# C_lula_2.net
KiCad netlist of a schematic drawn in Altium Designer
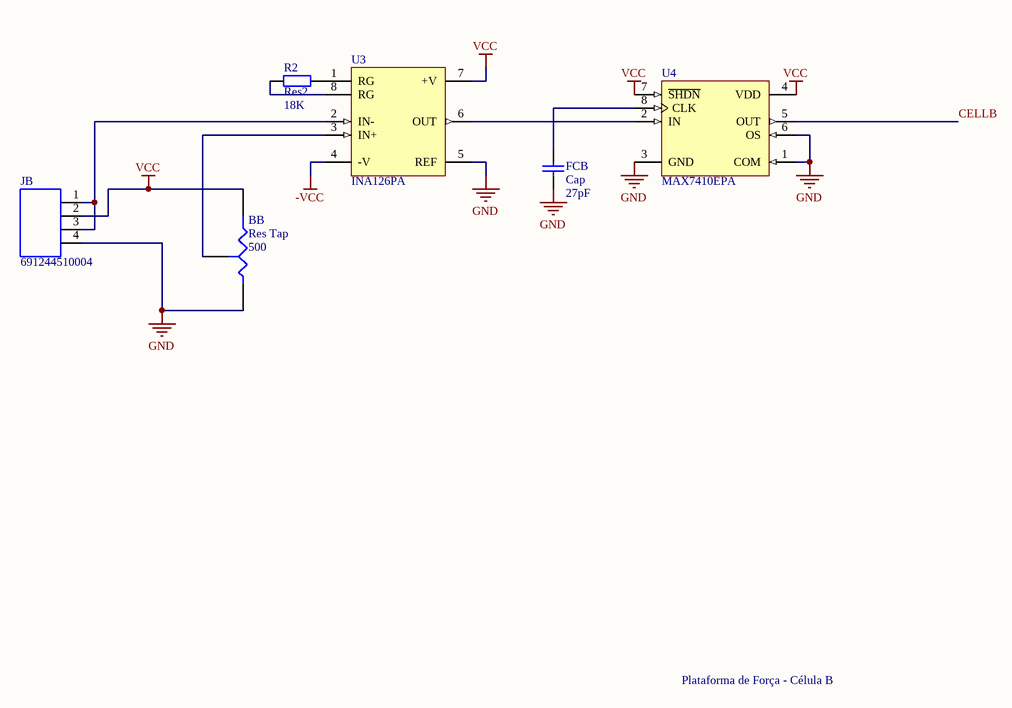
[diagram p0: Célula 2.SchDoc]

(export (version "E")
  (design (tool "Eeschema 10.0.6"))
  (components
    (comp (ref "BB")
      (value "Res Tap")
      (footprint "PcbLib1:TSR3006")
      (description "Tapped Resistor")
      (fields (field (name "ALTIUM_VALUE") "500") (field (name "PUBLISHER") "Altium Limited"))
      (libsource (lib "Miscellaneous Devices") (part "Res Tap"))
    )
    (comp (ref "FCB")
      (value "Cap")
      (footprint "RAD-0.3")
      (description "Capacitor")
      (fields (field (name "ALTIUM_VALUE") "27pF") (field (name "PUBLISHER") "Altium Limited"))
      (libsource (lib "Miscellaneous Devices") (part "Cap"))
    )
    (comp (ref "JB")
      (value "691244510004")
      (footprint "691244510004")
      (description "WR-TBL Horizontal Cable Entry With Rising Cage Clamp,Serie 2445 - 5.08 mm")
      (fields (field (name "MANUFACTURER") "Wurth Elektronik") (field (name "CREATED BY") "Baojun Chen"))
      (libsource (lib "WE_WR-TBL_Rising Cage System_5.08 mm_rev15b") (part "691244510004"))
    )
    (comp (ref "R2")
      (value "Res2")
      (footprint "AXIAL-0.4")
      (description "Resistor")
      (fields (field (name "ALTIUM_VALUE") "18K") (field (name "PUBLISHER") "Altium Limited"))
      (libsource (lib "Miscellaneous Devices") (part "Res2"))
    )
    (comp (ref "U3")
      (value "INA126PA")
      (footprint "006E")
      (description "Precision, Low-Power Instrumentation Amplifiers")
      (fields (field (name "PUBLISHER") "Altium Limited"))
      (libsource (lib "Placa") (part "INA126PA"))
    )
    (comp (ref "U4")
      (value "MAX7410EPA")
      (footprint "PA8")
      (description "5th-Order, Lowpass, Switched-Capacitor Filter")
      (fields (field (name "PUBLISHER") "Altium Limited"))
      (libsource (lib "Maxim Filter Switched Capacitor") (part "MAX7410EPA"))
    )
  )
  (nets
    (net (code "1") (name "-VCC") (class "Default")
      (node (ref "U3") (pin "4") (pinfunction "-V_4") (pintype "power_in"))
    )
    (net (code "2") (name "/CELLB") (class "Default")
      (node (ref "U4") (pin "5") (pinfunction "OUT_5") (pintype "output"))
    )
    (net (code "3") (name "GND") (class "Default")
      (node (ref "BB") (pin "1") (pinfunction "A_1") (pintype "passive"))
      (node (ref "FCB") (pin "1") (pinfunction "1_1") (pintype "passive"))
      (node (ref "JB") (pin "4") (pinfunction "4_4") (pintype "passive"))
      (node (ref "U3") (pin "5") (pinfunction "REF_5") (pintype "passive"))
      (node (ref "U4") (pin "1") (pinfunction "COM_1") (pintype "input"))
      (node (ref "U4") (pin "3") (pinfunction "GND_3") (pintype "power_in"))
      (node (ref "U4") (pin "6") (pinfunction "OS_6") (pintype "input"))
    )
    (net (code "4") (name "Net-(BB-TAP)") (class "Default")
      (node (ref "BB") (pin "3") (pinfunction "TAP_3") (pintype "passive"))
      (node (ref "U3") (pin "3") (pinfunction "IN+_3") (pintype "input"))
    )
    (net (code "5") (name "Net-(R2-Pad1)") (class "Default")
      (node (ref "R2") (pin "1") (pinfunction "1_1") (pintype "passive"))
      (node (ref "U3") (pin "8") (pinfunction "RG_8") (pintype "passive"))
    )
    (net (code "6") (name "Net-(R2-Pad2)") (class "Default")
      (node (ref "R2") (pin "2") (pinfunction "2_2") (pintype "passive"))
      (node (ref "U3") (pin "1") (pinfunction "RG_1") (pintype "passive"))
    )
    (net (code "7") (name "Net-(U3-IN-)") (class "Default")
      (node (ref "JB") (pin "1") (pinfunction "1_1") (pintype "passive"))
      (node (ref "JB") (pin "3") (pinfunction "3_3") (pintype "passive"))
      (node (ref "U3") (pin "2") (pinfunction "IN-_2") (pintype "input"))
    )
    (net (code "8") (name "Net-(U3-OUT)") (class "Default")
      (node (ref "U3") (pin "6") (pinfunction "OUT_6") (pintype "output"))
      (node (ref "U4") (pin "2") (pinfunction "IN_2") (pintype "input"))
    )
    (net (code "9") (name "Net-(U4-CLK)") (class "Default")
      (node (ref "FCB") (pin "2") (pinfunction "2_2") (pintype "passive"))
      (node (ref "U4") (pin "8") (pinfunction "CLK_8") (pintype "input"))
    )
    (net (code "10") (name "VCC") (class "Default")
      (node (ref "BB") (pin "2") (pinfunction "B_2") (pintype "passive"))
      (node (ref "JB") (pin "2") (pinfunction "2_2") (pintype "passive"))
      (node (ref "U3") (pin "7") (pinfunction "+V_7") (pintype "power_in"))
      (node (ref "U4") (pin "4") (pinfunction "VDD_4") (pintype "power_in"))
      (node (ref "U4") (pin "7") (pinfunction "~{SHDN}_7") (pintype "input"))
    )
  )
)
